# ProPrj_Usb_Hub_2026-05-24.net
KiCad netlist of a schematic drawn in EasyEDA Pro
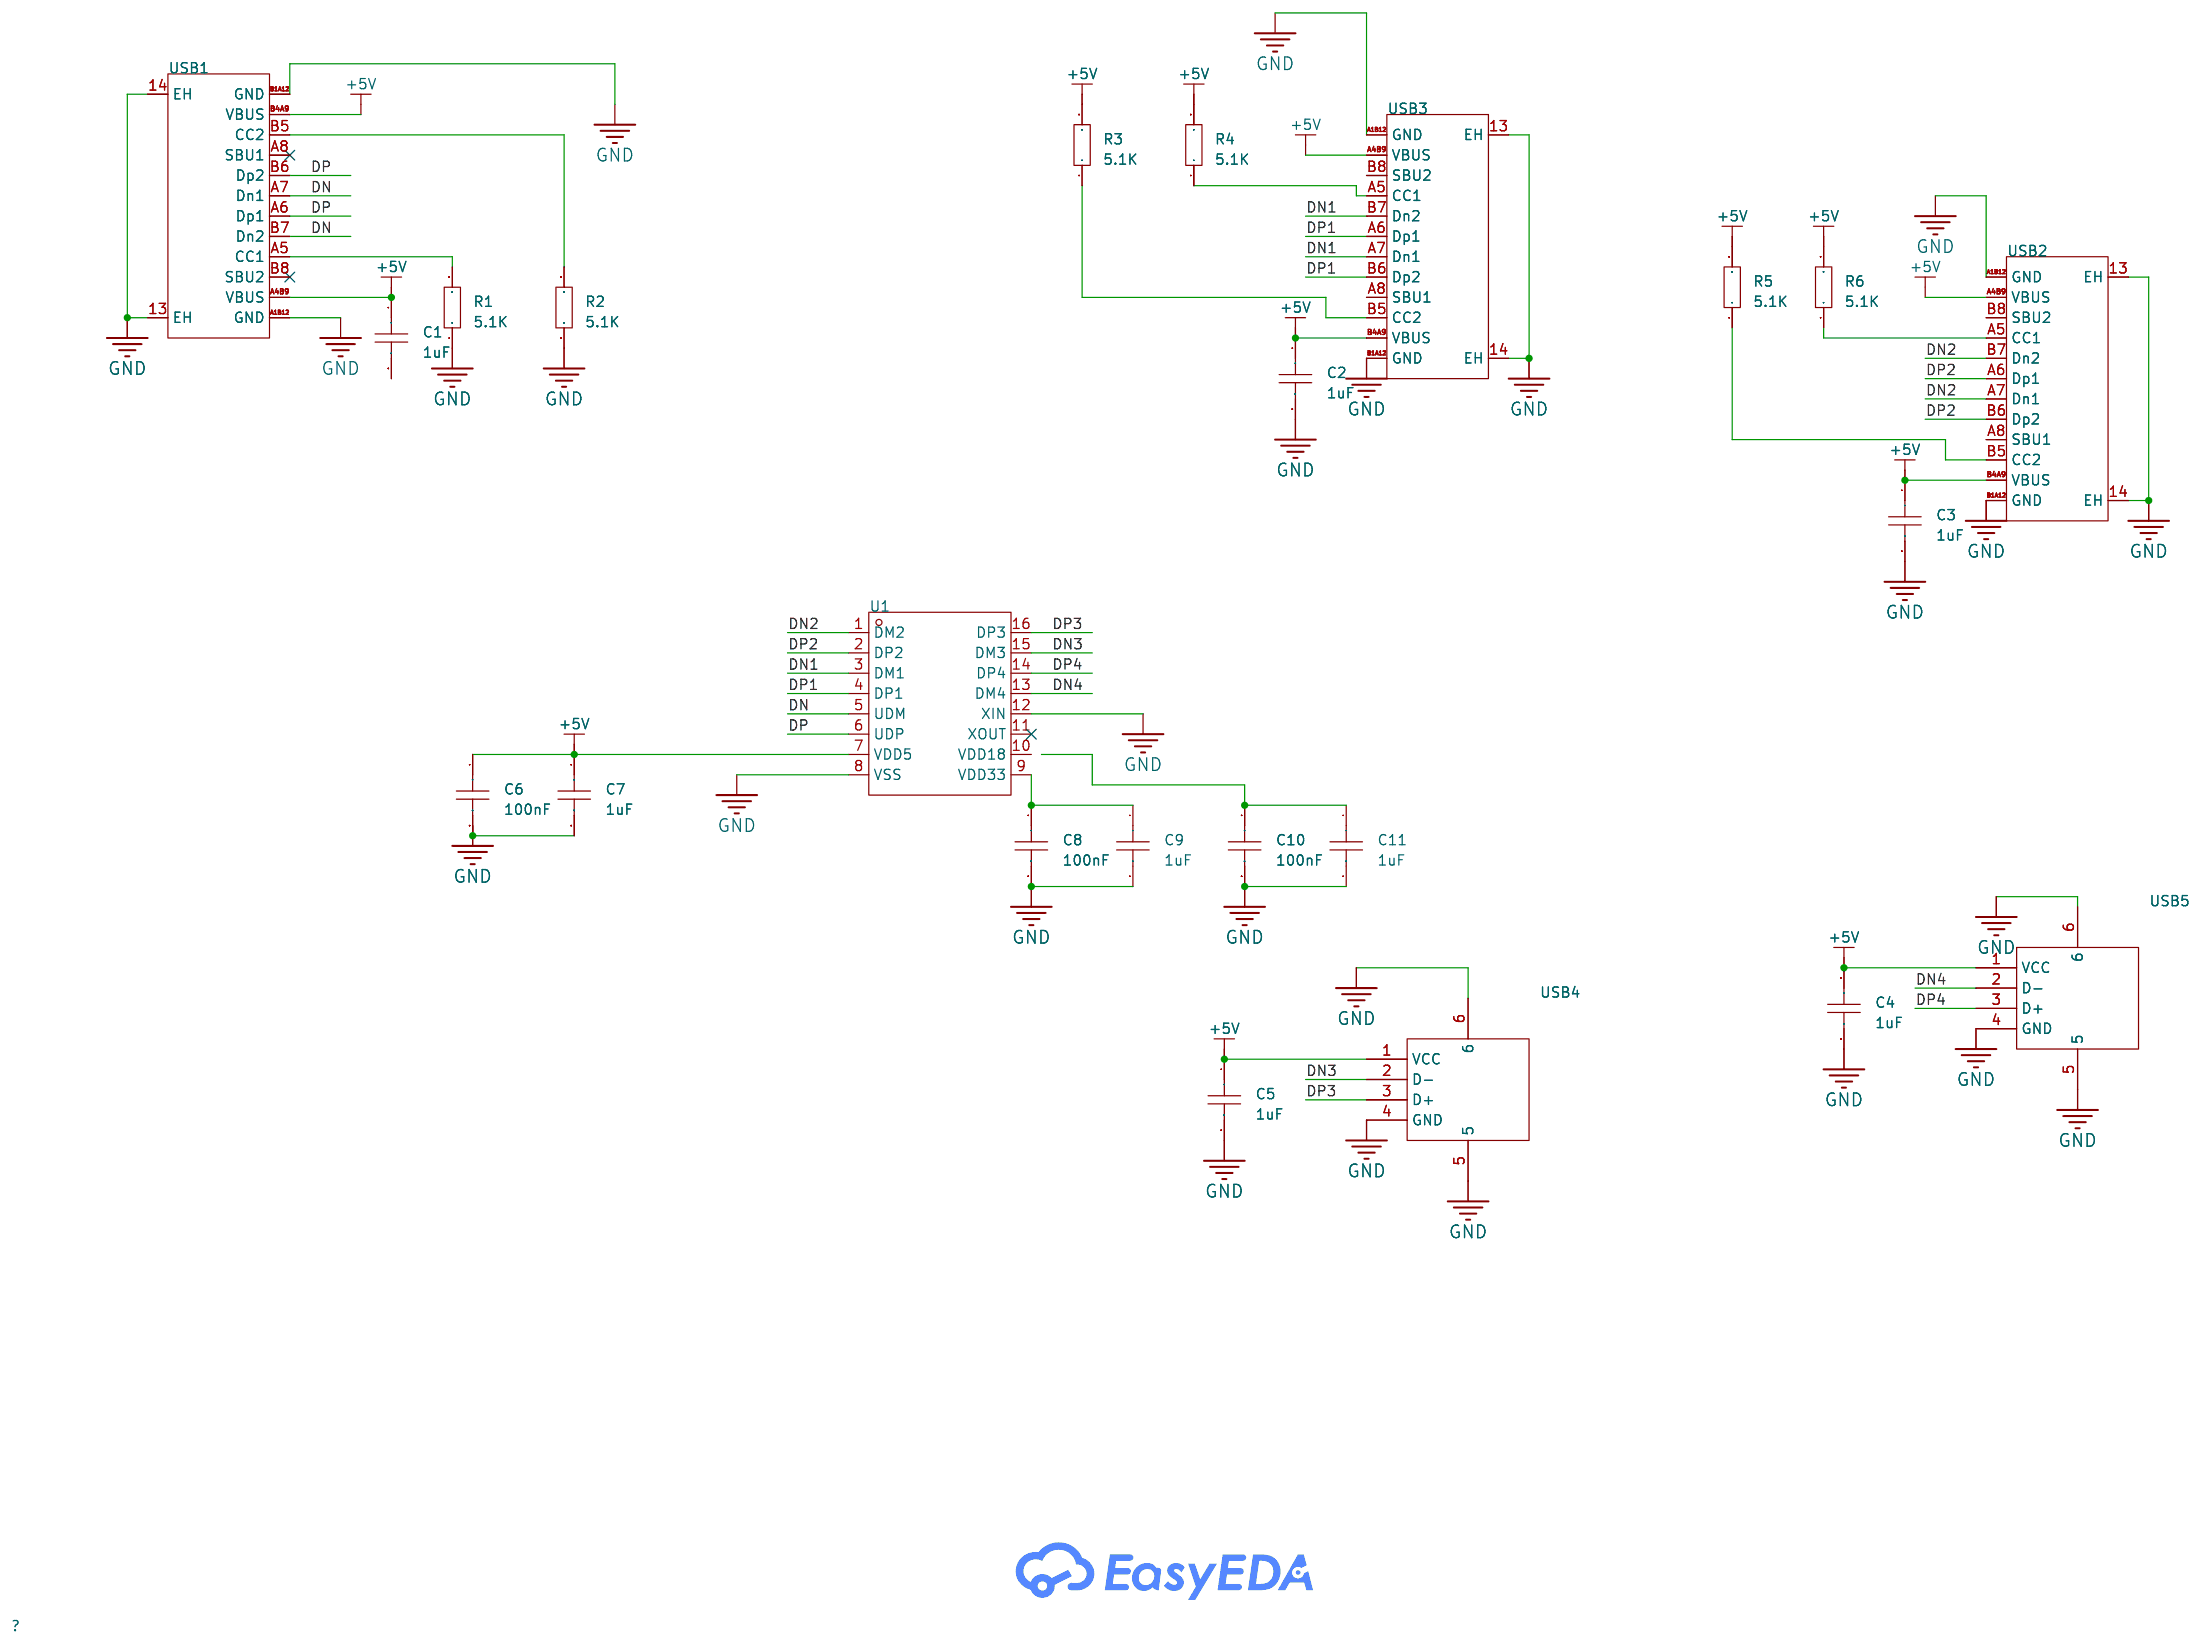
[diagram p0: schematic sheet]

(export (version "E")
  (design (tool "Eeschema 10.0.6"))
  (components
    (comp (ref "C1") (value "1uF") (footprint "easyedapro:C0603") (libsource (lib "easyedapro") (part "CAP")))
    (comp (ref "C2") (value "1uF") (footprint "easyedapro:C0603") (libsource (lib "easyedapro") (part "CAP")))
    (comp (ref "C3") (value "1uF") (footprint "easyedapro:C0603") (libsource (lib "easyedapro") (part "CAP")))
    (comp (ref "C4") (value "1uF") (footprint "easyedapro:C0603") (libsource (lib "easyedapro") (part "CAP")))
    (comp (ref "C5") (value "1uF") (footprint "easyedapro:C0603") (libsource (lib "easyedapro") (part "CAP")))
    (comp (ref "C6")
      (value "100nF")
      (footprint "easyedapro:C0603")
      (libsource (lib "easyedapro") (part "CAP"))
    )
    (comp (ref "C7") (value "1uF") (footprint "easyedapro:C0603") (libsource (lib "easyedapro") (part "CAP")))
    (comp (ref "C8")
      (value "100nF")
      (footprint "easyedapro:C0603")
      (libsource (lib "easyedapro") (part "CAP"))
    )
    (comp (ref "C9") (value "1uF") (footprint "easyedapro:C0603") (libsource (lib "easyedapro") (part "CAP")))
    (comp (ref "C10")
      (value "100nF")
      (footprint "easyedapro:C0603")
      (libsource (lib "easyedapro") (part "CAP"))
    )
    (comp (ref "C11")
      (value "1uF")
      (footprint "easyedapro:C0603")
      (libsource (lib "easyedapro") (part "CAP"))
    )
    (comp (ref "R1")
      (value "5.1K")
      (footprint "easyedapro:R0603")
      (libsource (lib "easyedapro") (part "Res"))
    )
    (comp (ref "R2")
      (value "5.1K")
      (footprint "easyedapro:R0603")
      (libsource (lib "easyedapro") (part "Res"))
    )
    (comp (ref "R3")
      (value "5.1K")
      (footprint "easyedapro:R0603")
      (libsource (lib "easyedapro") (part "Res"))
    )
    (comp (ref "R4")
      (value "5.1K")
      (footprint "easyedapro:R0603")
      (libsource (lib "easyedapro") (part "Res"))
    )
    (comp (ref "R5")
      (value "5.1K")
      (footprint "easyedapro:R0603")
      (libsource (lib "easyedapro") (part "Res"))
    )
    (comp (ref "R6")
      (value "5.1K")
      (footprint "easyedapro:R0603")
      (libsource (lib "easyedapro") (part "Res"))
    )
    (comp (ref "U1")
      (value "SL2.1s")
      (footprint "easyedapro:SSOP-16_L4.6-W2.6-P0.53-LS4.0-BL")
      (fields (field (name "Manufacturer") "CoreChips(和芯润德)"))
      (libsource (lib "easyedapro") (part "SL2.1S"))
    )
    (comp (ref "USB1")
      (value "TYPE-C 16PIN 2MD(073)")
      (footprint "easyedapro:USB-C-SMD_TYPE-C-16PIN-2MD-073")
      (fields (field (name "Manufacturer") "SHOU HAN(首韩)"))
      (libsource (lib "easyedapro") (part "TYPE-C 16PIN 2MD(073)"))
    )
    (comp (ref "USB2")
      (value "TYPE-C 16PIN 2MD(073)")
      (footprint "easyedapro:USB-C-SMD_TYPE-C-16PIN-2MD-073")
      (fields (field (name "Manufacturer") "SHOU HAN(首韩)"))
      (libsource (lib "easyedapro") (part "TYPE-C 16PIN 2MD(073)"))
    )
    (comp (ref "USB3")
      (value "TYPE-C 16PIN 2MD(073)")
      (footprint "easyedapro:USB-C-SMD_TYPE-C-16PIN-2MD-073")
      (fields (field (name "Manufacturer") "SHOU HAN(首韩)"))
      (libsource (lib "easyedapro") (part "TYPE-C 16PIN 2MD(073)"))
    )
    (comp (ref "USB4")
      (value "10.0 QHHTZB6.3")
      (footprint "easyedapro:USB-A-TH_10.0QHHTZB6.3")
      (fields (field (name "Manufacturer") "SHOU HAN(首韩)"))
      (libsource (lib "easyedapro") (part "10.0 QHHTZB6.3"))
    )
    (comp (ref "USB5")
      (value "10.0 QHHTZB6.3")
      (footprint "easyedapro:USB-A-TH_10.0QHHTZB6.3")
      (fields (field (name "Manufacturer") "SHOU HAN(首韩)"))
      (libsource (lib "easyedapro") (part "10.0 QHHTZB6.3"))
    )
  )
  (nets
    (net (code "1") (name "+5V") (class "Default")
      (node (ref "C1") (pin "1") (pinfunction "1_1") (pintype "input"))
      (node (ref "C2") (pin "1") (pinfunction "1_1") (pintype "input"))
      (node (ref "C3") (pin "1") (pinfunction "1_1") (pintype "input"))
      (node (ref "C4") (pin "1") (pinfunction "1_1") (pintype "input"))
      (node (ref "C5") (pin "1") (pinfunction "1_1") (pintype "input"))
      (node (ref "C6") (pin "1") (pinfunction "1_1") (pintype "input"))
      (node (ref "C7") (pin "1") (pinfunction "1_1") (pintype "input"))
      (node (ref "R3") (pin "2") (pinfunction "2_2") (pintype "input"))
      (node (ref "R4") (pin "2") (pinfunction "2_2") (pintype "input"))
      (node (ref "R5") (pin "2") (pinfunction "2_2") (pintype "input"))
      (node (ref "R6") (pin "2") (pinfunction "2_2") (pintype "input"))
      (node (ref "U1") (pin "7") (pinfunction "VDD5_7") (pintype "unspecified"))
      (node (ref "USB1") (pin "A4B9") (pinfunction "VBUS_A4B9") (pintype "unspecified"))
      (node (ref "USB1") (pin "B4A9") (pinfunction "VBUS_B4A9") (pintype "unspecified"))
      (node (ref "USB2") (pin "A4B9") (pinfunction "VBUS_A4B9") (pintype "unspecified"))
      (node (ref "USB2") (pin "B4A9") (pinfunction "VBUS_B4A9") (pintype "unspecified"))
      (node (ref "USB3") (pin "A4B9") (pinfunction "VBUS_A4B9") (pintype "unspecified"))
      (node (ref "USB3") (pin "B4A9") (pinfunction "VBUS_B4A9") (pintype "unspecified"))
      (node (ref "USB4") (pin "1") (pinfunction "VCC_1") (pintype "unspecified"))
      (node (ref "USB5") (pin "1") (pinfunction "VCC_1") (pintype "unspecified"))
    )
    (net (code "2") (name "/DN") (class "Default")
      (node (ref "U1") (pin "5") (pinfunction "UDM_5") (pintype "unspecified"))
      (node (ref "USB1") (pin "A7") (pinfunction "Dn1_A7") (pintype "unspecified"))
      (node (ref "USB1") (pin "B7") (pinfunction "Dn2_B7") (pintype "unspecified"))
    )
    (net (code "3") (name "/DN1") (class "Default")
      (node (ref "U1") (pin "3") (pinfunction "DM1_3") (pintype "unspecified"))
      (node (ref "USB3") (pin "A7") (pinfunction "Dn1_A7") (pintype "unspecified"))
      (node (ref "USB3") (pin "B7") (pinfunction "Dn2_B7") (pintype "unspecified"))
    )
    (net (code "4") (name "/DN2") (class "Default")
      (node (ref "U1") (pin "1") (pinfunction "DM2_1") (pintype "unspecified"))
      (node (ref "USB2") (pin "A7") (pinfunction "Dn1_A7") (pintype "unspecified"))
      (node (ref "USB2") (pin "B7") (pinfunction "Dn2_B7") (pintype "unspecified"))
    )
    (net (code "5") (name "/DN3") (class "Default")
      (node (ref "U1") (pin "15") (pinfunction "DM3_15") (pintype "unspecified"))
      (node (ref "USB4") (pin "2") (pinfunction "D-_2") (pintype "unspecified"))
    )
    (net (code "6") (name "/DN4") (class "Default")
      (node (ref "U1") (pin "13") (pinfunction "DM4_13") (pintype "unspecified"))
      (node (ref "USB5") (pin "2") (pinfunction "D-_2") (pintype "unspecified"))
    )
    (net (code "7") (name "/DP") (class "Default")
      (node (ref "U1") (pin "6") (pinfunction "UDP_6") (pintype "unspecified"))
      (node (ref "USB1") (pin "A6") (pinfunction "Dp1_A6") (pintype "unspecified"))
      (node (ref "USB1") (pin "B6") (pinfunction "Dp2_B6") (pintype "unspecified"))
    )
    (net (code "8") (name "/DP1") (class "Default")
      (node (ref "U1") (pin "4") (pinfunction "DP1_4") (pintype "unspecified"))
      (node (ref "USB3") (pin "A6") (pinfunction "Dp1_A6") (pintype "unspecified"))
      (node (ref "USB3") (pin "B6") (pinfunction "Dp2_B6") (pintype "unspecified"))
    )
    (net (code "9") (name "/DP2") (class "Default")
      (node (ref "U1") (pin "2") (pinfunction "DP2_2") (pintype "unspecified"))
      (node (ref "USB2") (pin "A6") (pinfunction "Dp1_A6") (pintype "unspecified"))
      (node (ref "USB2") (pin "B6") (pinfunction "Dp2_B6") (pintype "unspecified"))
    )
    (net (code "10") (name "/DP3") (class "Default")
      (node (ref "U1") (pin "16") (pinfunction "DP3_16") (pintype "unspecified"))
      (node (ref "USB4") (pin "3") (pinfunction "D+_3") (pintype "unspecified"))
    )
    (net (code "11") (name "/DP4") (class "Default")
      (node (ref "U1") (pin "14") (pinfunction "DP4_14") (pintype "unspecified"))
      (node (ref "USB5") (pin "3") (pinfunction "D+_3") (pintype "unspecified"))
    )
    (net (code "12") (name "GND") (class "Default")
      (node (ref "C10") (pin "2") (pinfunction "2_2") (pintype "input"))
      (node (ref "C11") (pin "2") (pinfunction "2_2") (pintype "input"))
      (node (ref "C2") (pin "2") (pinfunction "2_2") (pintype "input"))
      (node (ref "C3") (pin "2") (pinfunction "2_2") (pintype "input"))
      (node (ref "C4") (pin "2") (pinfunction "2_2") (pintype "input"))
      (node (ref "C5") (pin "2") (pinfunction "2_2") (pintype "input"))
      (node (ref "C6") (pin "2") (pinfunction "2_2") (pintype "input"))
      (node (ref "C7") (pin "2") (pinfunction "2_2") (pintype "input"))
      (node (ref "C8") (pin "2") (pinfunction "2_2") (pintype "input"))
      (node (ref "C9") (pin "2") (pinfunction "2_2") (pintype "input"))
      (node (ref "R1") (pin "1") (pinfunction "1_1") (pintype "input"))
      (node (ref "R2") (pin "1") (pinfunction "1_1") (pintype "input"))
      (node (ref "U1") (pin "12") (pinfunction "XIN_12") (pintype "unspecified"))
      (node (ref "U1") (pin "8") (pinfunction "VSS_8") (pintype "unspecified"))
      (node (ref "USB1") (pin "13") (pinfunction "EH_13") (pintype "unspecified"))
      (node (ref "USB1") (pin "14") (pinfunction "EH_14") (pintype "unspecified"))
      (node (ref "USB1") (pin "A1B12") (pinfunction "GND_A1B12") (pintype "unspecified"))
      (node (ref "USB1") (pin "B1A12") (pinfunction "GND_B1A12") (pintype "unspecified"))
      (node (ref "USB2") (pin "13") (pinfunction "EH_13") (pintype "unspecified"))
      (node (ref "USB2") (pin "14") (pinfunction "EH_14") (pintype "unspecified"))
      (node (ref "USB2") (pin "A1B12") (pinfunction "GND_A1B12") (pintype "unspecified"))
      (node (ref "USB2") (pin "B1A12") (pinfunction "GND_B1A12") (pintype "unspecified"))
      (node (ref "USB3") (pin "13") (pinfunction "EH_13") (pintype "unspecified"))
      (node (ref "USB3") (pin "14") (pinfunction "EH_14") (pintype "unspecified"))
      (node (ref "USB3") (pin "A1B12") (pinfunction "GND_A1B12") (pintype "unspecified"))
      (node (ref "USB3") (pin "B1A12") (pinfunction "GND_B1A12") (pintype "unspecified"))
      (node (ref "USB4") (pin "4") (pinfunction "GND_4") (pintype "unspecified"))
      (node (ref "USB4") (pin "5") (pinfunction "5_5") (pintype "unspecified"))
      (node (ref "USB4") (pin "6") (pinfunction "6_6") (pintype "unspecified"))
      (node (ref "USB5") (pin "4") (pinfunction "GND_4") (pintype "unspecified"))
      (node (ref "USB5") (pin "5") (pinfunction "5_5") (pintype "unspecified"))
      (node (ref "USB5") (pin "6") (pinfunction "6_6") (pintype "unspecified"))
    )
    (net (code "13") (name "Net-(C10-Pad1)") (class "Default")
      (node (ref "C10") (pin "1") (pinfunction "1_1") (pintype "input"))
      (node (ref "C11") (pin "1") (pinfunction "1_1") (pintype "input"))
    )
    (net (code "14") (name "Net-(U1-VDD33)") (class "Default")
      (node (ref "C8") (pin "1") (pinfunction "1_1") (pintype "input"))
      (node (ref "C9") (pin "1") (pinfunction "1_1") (pintype "input"))
      (node (ref "U1") (pin "9") (pinfunction "VDD33_9") (pintype "unspecified"))
    )
    (net (code "15") (name "Net-(USB1-CC1)") (class "Default")
      (node (ref "R1") (pin "2") (pinfunction "2_2") (pintype "input"))
      (node (ref "USB1") (pin "A5") (pinfunction "CC1_A5") (pintype "unspecified"))
    )
    (net (code "16") (name "Net-(USB1-CC2)") (class "Default")
      (node (ref "R2") (pin "2") (pinfunction "2_2") (pintype "input"))
      (node (ref "USB1") (pin "B5") (pinfunction "CC2_B5") (pintype "unspecified"))
    )
    (net (code "17") (name "Net-(USB2-CC1)") (class "Default")
      (node (ref "R6") (pin "1") (pinfunction "1_1") (pintype "input"))
      (node (ref "USB2") (pin "A5") (pinfunction "CC1_A5") (pintype "unspecified"))
    )
    (net (code "18") (name "Net-(USB2-CC2)") (class "Default")
      (node (ref "R5") (pin "1") (pinfunction "1_1") (pintype "input"))
      (node (ref "USB2") (pin "B5") (pinfunction "CC2_B5") (pintype "unspecified"))
    )
    (net (code "19") (name "Net-(USB3-CC1)") (class "Default")
      (node (ref "R4") (pin "1") (pinfunction "1_1") (pintype "input"))
      (node (ref "USB3") (pin "A5") (pinfunction "CC1_A5") (pintype "unspecified"))
    )
    (net (code "20") (name "Net-(USB3-CC2)") (class "Default")
      (node (ref "R3") (pin "1") (pinfunction "1_1") (pintype "input"))
      (node (ref "USB3") (pin "B5") (pinfunction "CC2_B5") (pintype "unspecified"))
    )
    (net (code "21") (name "unconnected-(C1-Pad2)") (class "Default")
      (node (ref "C1") (pin "2") (pinfunction "2_2") (pintype "input"))
    )
    (net (code "22") (name "unconnected-(U1-VDD18-Pad10)") (class "Default")
      (node (ref "U1") (pin "10") (pinfunction "VDD18_10") (pintype "unspecified"))
    )
    (net (code "23") (name "unconnected-(U1-XOUT-Pad11)") (class "Default")
      (node (ref "U1") (pin "11") (pinfunction "XOUT_11") (pintype "unspecified+no_connect"))
    )
    (net (code "24") (name "unconnected-(USB1-SBU1-PadA8)") (class "Default")
      (node (ref "USB1") (pin "A8") (pinfunction "SBU1_A8") (pintype "unspecified+no_connect"))
    )
    (net (code "25") (name "unconnected-(USB1-SBU2-PadB8)") (class "Default")
      (node (ref "USB1") (pin "B8") (pinfunction "SBU2_B8") (pintype "unspecified+no_connect"))
    )
    (net (code "26") (name "unconnected-(USB2-SBU1-PadA8)") (class "Default")
      (node (ref "USB2") (pin "A8") (pinfunction "SBU1_A8") (pintype "unspecified"))
    )
    (net (code "27") (name "unconnected-(USB2-SBU2-PadB8)") (class "Default")
      (node (ref "USB2") (pin "B8") (pinfunction "SBU2_B8") (pintype "unspecified"))
    )
    (net (code "28") (name "unconnected-(USB3-SBU1-PadA8)") (class "Default")
      (node (ref "USB3") (pin "A8") (pinfunction "SBU1_A8") (pintype "unspecified"))
    )
    (net (code "29") (name "unconnected-(USB3-SBU2-PadB8)") (class "Default")
      (node (ref "USB3") (pin "B8") (pinfunction "SBU2_B8") (pintype "unspecified"))
    )
  )
)
